# Puzzle_-_Infrared_Reflective_Sensor.net
KiCad netlist of a schematic drawn in EAGLE
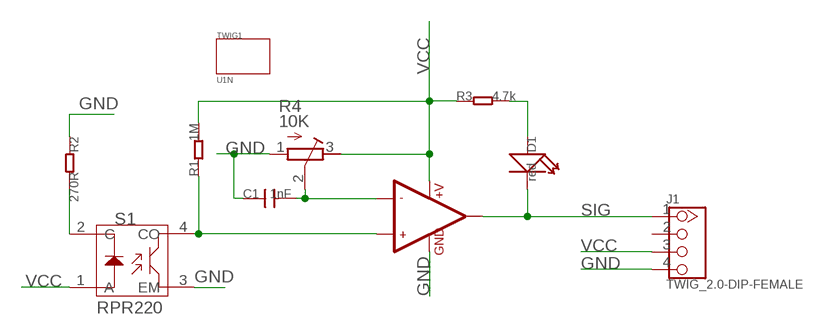
[diagram p0: schematic, sheet 1]

(export (version "E")
  (design (tool "Eeschema 10.0.6"))
  (components
    (comp (ref "C1")
      (value "1nF")
      (footprint "eagle-import:0603")
      (libsource (lib "eagle-import") (part "C-0603"))
    )
    (comp (ref "D1")
      (value "red")
      (footprint "eagle-import:LED0603")
      (libsource (lib "eagle-import") (part "007-LED3540"))
    )
    (comp (ref "J1")
      (value "TWIG_2.0-DIP-FEMALE")
      (footprint "eagle-import:2.0_1X4")
      (libsource (lib "eagle-import") (part "TWIG_2.0-DIP-FEMALE"))
    )
    (comp (ref "R1")
      (value "1M")
      (footprint "eagle-import:0603_S")
      (libsource (lib "eagle-import") (part "005-R0603_S"))
    )
    (comp (ref "R2")
      (value "270R")
      (footprint "eagle-import:0603_S")
      (libsource (lib "eagle-import") (part "005-R0603_S"))
    )
    (comp (ref "R3")
      (value "4.7k")
      (footprint "eagle-import:0603_S")
      (libsource (lib "eagle-import") (part "005-R0603_S"))
    )
    (comp (ref "R4")
      (value "10K")
      (footprint "eagle-import:RTRIM3214W")
      (libsource (lib "eagle-import") (part "R-TRIMM3214W"))
    )
    (comp (ref "S1")
      (value "RPR220")
      (footprint "eagle-import:4P-6.4X4.9X6.5H")
      (libsource (lib "eagle-import") (part "REFLECTIVE-PHOTOSENSOR-RPR-220"))
    )
    (comp (ref "TWIG1")
      (value "U1N")
      (footprint "eagle-import:U1N")
      (libsource (lib "eagle-import") (part "U1N"))
    )
    (comp (ref "U1")
      (value "002-LMV358")
      (footprint "eagle-import:SO08")
      (libsource (lib "eagle-import") (part "002-LMV358"))
    )
  )
  (nets
    (net (code "1") (name "/GND") (class "Default")
      (node (ref "C1") (pin "1") (pinfunction "1_1") (pintype "passive"))
      (node (ref "J1") (pin "4") (pinfunction "4_4") (pintype "bidirectional"))
      (node (ref "R2") (pin "1") (pinfunction "1_1") (pintype "passive"))
      (node (ref "R4") (pin "1") (pinfunction "E_1") (pintype "passive"))
      (node (ref "S1") (pin "3") (pinfunction "EM_3") (pintype "bidirectional"))
      (node (ref "U1") (pin "4") (pinfunction "GND_4") (pintype "power_in"))
    )
    (net (code "2") (name "/SIG") (class "Default")
      (node (ref "D1") (pin "2") (pinfunction "-_2") (pintype "passive"))
      (node (ref "J1") (pin "1") (pinfunction "1_1") (pintype "bidirectional"))
      (node (ref "U1") (pin "1") (pinfunction "OUT1_1") (pintype "output"))
    )
    (net (code "3") (name "/VCC") (class "Default")
      (node (ref "J1") (pin "3") (pinfunction "3_3") (pintype "bidirectional"))
      (node (ref "R1") (pin "2") (pinfunction "2_2") (pintype "passive"))
      (node (ref "R3") (pin "1") (pinfunction "1_1") (pintype "passive"))
      (node (ref "R4") (pin "3") (pinfunction "A_3") (pintype "passive"))
      (node (ref "S1") (pin "1") (pinfunction "A_1") (pintype "bidirectional"))
      (node (ref "U1") (pin "8") (pinfunction "+V_8") (pintype "power_in"))
    )
    (net (code "4") (name "Net-(D1-+)") (class "Default")
      (node (ref "D1") (pin "1") (pinfunction "+_1") (pintype "passive"))
      (node (ref "R3") (pin "2") (pinfunction "2_2") (pintype "passive"))
    )
    (net (code "5") (name "Net-(R4-S)") (class "Default")
      (node (ref "C1") (pin "2") (pinfunction "2_2") (pintype "passive"))
      (node (ref "R4") (pin "2") (pinfunction "S_2") (pintype "passive"))
      (node (ref "U1") (pin "2") (pinfunction "-IN1_2") (pintype "input"))
    )
    (net (code "6") (name "Net-(S1-C)") (class "Default")
      (node (ref "R2") (pin "2") (pinfunction "2_2") (pintype "passive"))
      (node (ref "S1") (pin "2") (pinfunction "C_2") (pintype "bidirectional"))
    )
    (net (code "7") (name "Net-(S1-CO)") (class "Default")
      (node (ref "R1") (pin "1") (pinfunction "1_1") (pintype "passive"))
      (node (ref "S1") (pin "4") (pinfunction "CO_4") (pintype "bidirectional"))
      (node (ref "U1") (pin "3") (pinfunction "+IN1_3") (pintype "input"))
    )
    (net (code "8") (name "unconnected-(J1-Pad2)") (class "Default")
      (node (ref "J1") (pin "2") (pinfunction "2_2") (pintype "bidirectional"))
    )
  )
)
